# ProPrj_Motorcycle_Controller_2026-08-31.net
KiCad netlist of a schematic drawn in EasyEDA Pro
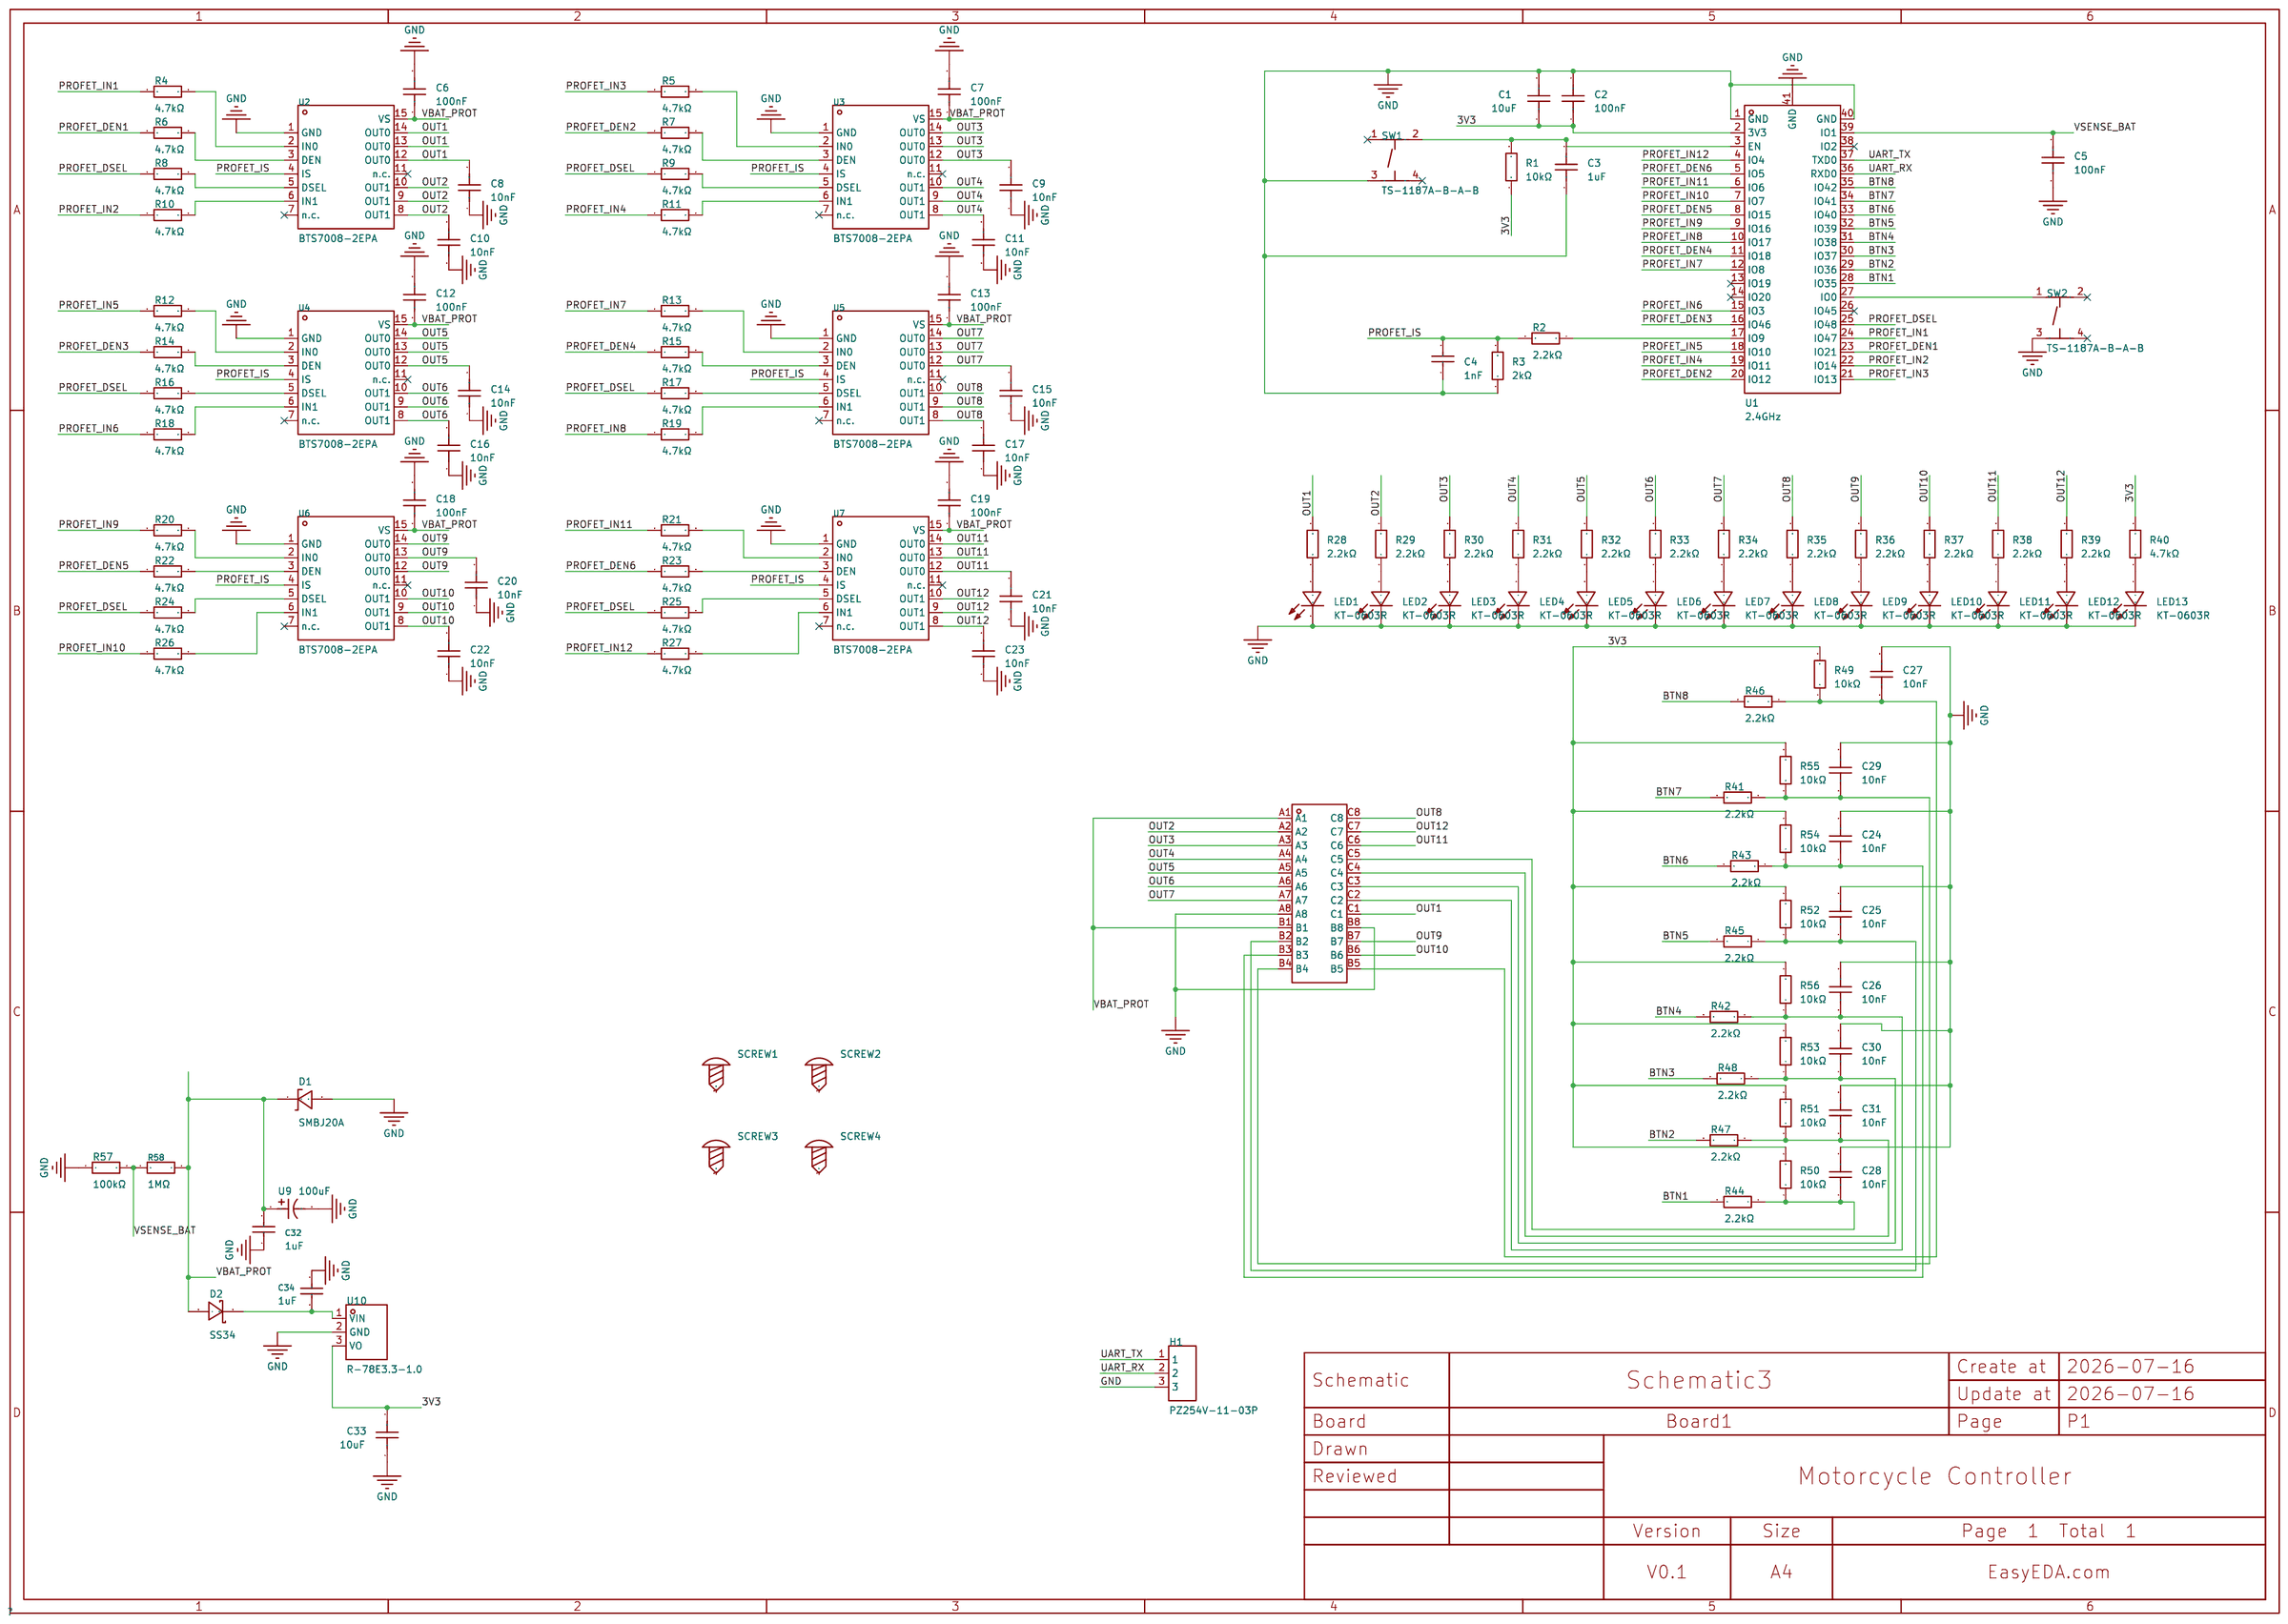
[diagram p0: schematic sheet]

(export (version "E")
  (design (tool "Eeschema 10.0.6"))
  (components
    (comp (ref "C1")
      (value "10uF")
      (footprint "easyedapro:C0603")
      (fields
        (field (name "Manufacturer Part") "CL10A106KP8NNNC")
        (field (name "Manufacturer") "SAMSUNG(三星)")
      )
      (libsource (lib "easyedapro") (part "CL10A106KP8NNNC"))
    )
    (comp (ref "C2")
      (value "100nF")
      (footprint "easyedapro:C0402")
      (fields
        (field (name "Manufacturer Part") "CL05B104KO5NNNC")
        (field (name "Manufacturer") "SAMSUNG(三星)")
      )
      (libsource (lib "easyedapro") (part "CL05B104KO5NNNC"))
    )
    (comp (ref "C3")
      (value "1uF")
      (footprint "easyedapro:C0402")
      (fields
        (field (name "Manufacturer Part") "CL05A105KA5NQNC")
        (field (name "Manufacturer") "SAMSUNG(三星)")
      )
      (libsource (lib "easyedapro") (part "CL05A105KA5NQNC"))
    )
    (comp (ref "C4")
      (value "1nF")
      (footprint "easyedapro:C0402")
      (fields (field (name "Manufacturer Part") "0402B102K500NT") (field (name "Manufacturer") "FH(风华)"))
      (libsource (lib "easyedapro") (part "0402B102K500NT"))
    )
    (comp (ref "C5")
      (value "100nF")
      (footprint "easyedapro:C0402")
      (fields
        (field (name "Manufacturer Part") "CL05B104KO5NNNC")
        (field (name "Manufacturer") "SAMSUNG(三星)")
      )
      (libsource (lib "easyedapro") (part "CL05B104KO5NNNC"))
    )
    (comp (ref "C6")
      (value "100nF")
      (footprint "easyedapro:C0603")
      (fields
        (field (name "Manufacturer Part") "CC0603KRX7R9BB104")
        (field (name "Manufacturer") "YAGEO(国巨)")
      )
      (libsource (lib "easyedapro") (part "CC0603KRX7R9BB104"))
    )
    (comp (ref "C7")
      (value "100nF")
      (footprint "easyedapro:C0603")
      (fields
        (field (name "Manufacturer Part") "CC0603KRX7R9BB104")
        (field (name "Manufacturer") "YAGEO(国巨)")
      )
      (libsource (lib "easyedapro") (part "CC0603KRX7R9BB104"))
    )
    (comp (ref "C8")
      (value "10nF")
      (footprint "easyedapro:C0603")
      (fields (field (name "Manufacturer Part") "0603B103K500NT") (field (name "Manufacturer") "FH(风华)"))
      (libsource (lib "easyedapro") (part "0603B103K500NT"))
    )
    (comp (ref "C9")
      (value "10nF")
      (footprint "easyedapro:C0603")
      (fields (field (name "Manufacturer Part") "0603B103K500NT") (field (name "Manufacturer") "FH(风华)"))
      (libsource (lib "easyedapro") (part "0603B103K500NT"))
    )
    (comp (ref "C10")
      (value "10nF")
      (footprint "easyedapro:C0603")
      (fields (field (name "Manufacturer Part") "0603B103K500NT") (field (name "Manufacturer") "FH(风华)"))
      (libsource (lib "easyedapro") (part "0603B103K500NT"))
    )
    (comp (ref "C11")
      (value "10nF")
      (footprint "easyedapro:C0603")
      (fields (field (name "Manufacturer Part") "0603B103K500NT") (field (name "Manufacturer") "FH(风华)"))
      (libsource (lib "easyedapro") (part "0603B103K500NT"))
    )
    (comp (ref "C12")
      (value "100nF")
      (footprint "easyedapro:C0603")
      (fields
        (field (name "Manufacturer Part") "CC0603KRX7R9BB104")
        (field (name "Manufacturer") "YAGEO(国巨)")
      )
      (libsource (lib "easyedapro") (part "CC0603KRX7R9BB104"))
    )
    (comp (ref "C13")
      (value "100nF")
      (footprint "easyedapro:C0603")
      (fields
        (field (name "Manufacturer Part") "CC0603KRX7R9BB104")
        (field (name "Manufacturer") "YAGEO(国巨)")
      )
      (libsource (lib "easyedapro") (part "CC0603KRX7R9BB104"))
    )
    (comp (ref "C14")
      (value "10nF")
      (footprint "easyedapro:C0603")
      (fields (field (name "Manufacturer Part") "0603B103K500NT") (field (name "Manufacturer") "FH(风华)"))
      (libsource (lib "easyedapro") (part "0603B103K500NT"))
    )
    (comp (ref "C15")
      (value "10nF")
      (footprint "easyedapro:C0603")
      (fields (field (name "Manufacturer Part") "0603B103K500NT") (field (name "Manufacturer") "FH(风华)"))
      (libsource (lib "easyedapro") (part "0603B103K500NT"))
    )
    (comp (ref "C16")
      (value "10nF")
      (footprint "easyedapro:C0603")
      (fields (field (name "Manufacturer Part") "0603B103K500NT") (field (name "Manufacturer") "FH(风华)"))
      (libsource (lib "easyedapro") (part "0603B103K500NT"))
    )
    (comp (ref "C17")
      (value "10nF")
      (footprint "easyedapro:C0603")
      (fields (field (name "Manufacturer Part") "0603B103K500NT") (field (name "Manufacturer") "FH(风华)"))
      (libsource (lib "easyedapro") (part "0603B103K500NT"))
    )
    (comp (ref "C18")
      (value "100nF")
      (footprint "easyedapro:C0603")
      (fields
        (field (name "Manufacturer Part") "CC0603KRX7R9BB104")
        (field (name "Manufacturer") "YAGEO(国巨)")
      )
      (libsource (lib "easyedapro") (part "CC0603KRX7R9BB104"))
    )
    (comp (ref "C19")
      (value "100nF")
      (footprint "easyedapro:C0603")
      (fields
        (field (name "Manufacturer Part") "CC0603KRX7R9BB104")
        (field (name "Manufacturer") "YAGEO(国巨)")
      )
      (libsource (lib "easyedapro") (part "CC0603KRX7R9BB104"))
    )
    (comp (ref "C20")
      (value "10nF")
      (footprint "easyedapro:C0603")
      (fields (field (name "Manufacturer Part") "0603B103K500NT") (field (name "Manufacturer") "FH(风华)"))
      (libsource (lib "easyedapro") (part "0603B103K500NT"))
    )
    (comp (ref "C21")
      (value "10nF")
      (footprint "easyedapro:C0603")
      (fields (field (name "Manufacturer Part") "0603B103K500NT") (field (name "Manufacturer") "FH(风华)"))
      (libsource (lib "easyedapro") (part "0603B103K500NT"))
    )
    (comp (ref "C22")
      (value "10nF")
      (footprint "easyedapro:C0603")
      (fields (field (name "Manufacturer Part") "0603B103K500NT") (field (name "Manufacturer") "FH(风华)"))
      (libsource (lib "easyedapro") (part "0603B103K500NT"))
    )
    (comp (ref "C23")
      (value "10nF")
      (footprint "easyedapro:C0603")
      (fields (field (name "Manufacturer Part") "0603B103K500NT") (field (name "Manufacturer") "FH(风华)"))
      (libsource (lib "easyedapro") (part "0603B103K500NT"))
    )
    (comp (ref "C24")
      (value "10nF")
      (footprint "easyedapro:C0603")
      (fields (field (name "Manufacturer Part") "0603B103K500NT") (field (name "Manufacturer") "FH(风华)"))
      (libsource (lib "easyedapro") (part "0603B103K500NT"))
    )
    (comp (ref "C25")
      (value "10nF")
      (footprint "easyedapro:C0603")
      (fields (field (name "Manufacturer Part") "0603B103K500NT") (field (name "Manufacturer") "FH(风华)"))
      (libsource (lib "easyedapro") (part "0603B103K500NT"))
    )
    (comp (ref "C26")
      (value "10nF")
      (footprint "easyedapro:C0603")
      (fields (field (name "Manufacturer Part") "0603B103K500NT") (field (name "Manufacturer") "FH(风华)"))
      (libsource (lib "easyedapro") (part "0603B103K500NT"))
    )
    (comp (ref "C27")
      (value "10nF")
      (footprint "easyedapro:C0603")
      (fields (field (name "Manufacturer Part") "0603B103K500NT") (field (name "Manufacturer") "FH(风华)"))
      (libsource (lib "easyedapro") (part "0603B103K500NT"))
    )
    (comp (ref "C28")
      (value "10nF")
      (footprint "easyedapro:C0603")
      (fields (field (name "Manufacturer Part") "0603B103K500NT") (field (name "Manufacturer") "FH(风华)"))
      (libsource (lib "easyedapro") (part "0603B103K500NT"))
    )
    (comp (ref "C29")
      (value "10nF")
      (footprint "easyedapro:C0603")
      (fields (field (name "Manufacturer Part") "0603B103K500NT") (field (name "Manufacturer") "FH(风华)"))
      (libsource (lib "easyedapro") (part "0603B103K500NT"))
    )
    (comp (ref "C30")
      (value "10nF")
      (footprint "easyedapro:C0603")
      (fields (field (name "Manufacturer Part") "0603B103K500NT") (field (name "Manufacturer") "FH(风华)"))
      (libsource (lib "easyedapro") (part "0603B103K500NT"))
    )
    (comp (ref "C31")
      (value "10nF")
      (footprint "easyedapro:C0603")
      (fields (field (name "Manufacturer Part") "0603B103K500NT") (field (name "Manufacturer") "FH(风华)"))
      (libsource (lib "easyedapro") (part "0603B103K500NT"))
    )
    (comp (ref "C32")
      (value "1uF")
      (footprint "easyedapro:C0805")
      (fields
        (field (name "Manufacturer Part") "CL21B105KBFNNNE")
        (field (name "Manufacturer") "SAMSUNG(三星)")
      )
      (libsource (lib "easyedapro") (part "CL21B105KBFNNNE"))
    )
    (comp (ref "C33")
      (value "10uF")
      (footprint "easyedapro:C0603")
      (fields
        (field (name "Manufacturer Part") "CL10A106KP8NNNC")
        (field (name "Manufacturer") "SAMSUNG(三星)")
      )
      (libsource (lib "easyedapro") (part "CL10A106KP8NNNC"))
    )
    (comp (ref "C34")
      (value "1uF")
      (footprint "easyedapro:C0805")
      (fields
        (field (name "Manufacturer Part") "CL21B105KBFNNNE")
        (field (name "Manufacturer") "SAMSUNG(三星)")
      )
      (libsource (lib "easyedapro") (part "CL21B105KBFNNNE"))
    )
    (comp (ref "CN3")
      (value "HCCPHPE24BKA90F")
      (footprint "easyedapro:CONN-TH_HCCPHPE24BKA90F")
      (fields (field (name "Manufacturer") "Aptiv(Delphi)"))
      (libsource (lib "easyedapro") (part "HCCPHPE24BKA90F_C5349068"))
    )
    (comp (ref "D1")
      (value "SMBJ20A")
      (footprint "easyedapro:SMB_L4.6-W3.6-LS5.3-RD")
      (fields (field (name "Manufacturer") "MDD(辰达半导体)"))
      (libsource (lib "easyedapro") (part "SMBJ20A_C364296"))
    )
    (comp (ref "D2")
      (value "SS34")
      (footprint "easyedapro:SMA_L4.3-W2.6-LS5.2-RD")
      (fields (field (name "Manufacturer") "MDD(辰达半导体)"))
      (libsource (lib "easyedapro") (part "SS34_C8678"))
    )
    (comp (ref "H1")
      (value "PZ254V-11-03P")
      (footprint "easyedapro:HDR-TH_3P-P2.54-V-M_PZ254V-11-03P")
      (fields (field (name "Manufacturer") "XFCN(兴飞)"))
      (libsource (lib "easyedapro") (part "PZ254V-11-03P_C2937625"))
    )
    (comp (ref "LED1")
      (value "KT-0603R")
      (footprint "easyedapro:LED-SMD_L1.6-W0.8-R-RD")
      (fields (field (name "Manufacturer") "KENTO"))
      (libsource (lib "easyedapro") (part "KT-0603R"))
    )
    (comp (ref "LED2")
      (value "KT-0603R")
      (footprint "easyedapro:LED-SMD_L1.6-W0.8-R-RD")
      (fields (field (name "Manufacturer") "KENTO"))
      (libsource (lib "easyedapro") (part "KT-0603R"))
    )
    (comp (ref "LED3")
      (value "KT-0603R")
      (footprint "easyedapro:LED-SMD_L1.6-W0.8-R-RD")
      (fields (field (name "Manufacturer") "KENTO"))
      (libsource (lib "easyedapro") (part "KT-0603R"))
    )
    (comp (ref "LED4")
      (value "KT-0603R")
      (footprint "easyedapro:LED-SMD_L1.6-W0.8-R-RD")
      (fields (field (name "Manufacturer") "KENTO"))
      (libsource (lib "easyedapro") (part "KT-0603R"))
    )
    (comp (ref "LED5")
      (value "KT-0603R")
      (footprint "easyedapro:LED-SMD_L1.6-W0.8-R-RD")
      (fields (field (name "Manufacturer") "KENTO"))
      (libsource (lib "easyedapro") (part "KT-0603R"))
    )
    (comp (ref "LED6")
      (value "KT-0603R")
      (footprint "easyedapro:LED-SMD_L1.6-W0.8-R-RD")
      (fields (field (name "Manufacturer") "KENTO"))
      (libsource (lib "easyedapro") (part "KT-0603R"))
    )
    (comp (ref "LED7")
      (value "KT-0603R")
      (footprint "easyedapro:LED-SMD_L1.6-W0.8-R-RD")
      (fields (field (name "Manufacturer") "KENTO"))
      (libsource (lib "easyedapro") (part "KT-0603R"))
    )
    (comp (ref "LED8")
      (value "KT-0603R")
      (footprint "easyedapro:LED-SMD_L1.6-W0.8-R-RD")
      (fields (field (name "Manufacturer") "KENTO"))
      (libsource (lib "easyedapro") (part "KT-0603R"))
    )
    (comp (ref "LED9")
      (value "KT-0603R")
      (footprint "easyedapro:LED-SMD_L1.6-W0.8-R-RD")
      (fields (field (name "Manufacturer") "KENTO"))
      (libsource (lib "easyedapro") (part "KT-0603R"))
    )
    (comp (ref "LED10")
      (value "KT-0603R")
      (footprint "easyedapro:LED-SMD_L1.6-W0.8-R-RD")
      (fields (field (name "Manufacturer") "KENTO"))
      (libsource (lib "easyedapro") (part "KT-0603R"))
    )
    (comp (ref "LED11")
      (value "KT-0603R")
      (footprint "easyedapro:LED-SMD_L1.6-W0.8-R-RD")
      (fields (field (name "Manufacturer") "KENTO"))
      (libsource (lib "easyedapro") (part "KT-0603R"))
    )
    (comp (ref "LED12")
      (value "KT-0603R")
      (footprint "easyedapro:LED-SMD_L1.6-W0.8-R-RD")
      (fields (field (name "Manufacturer") "KENTO"))
      (libsource (lib "easyedapro") (part "KT-0603R"))
    )
    (comp (ref "LED13")
      (value "KT-0603R")
      (footprint "easyedapro:LED-SMD_L1.6-W0.8-R-RD")
      (fields (field (name "Manufacturer") "KENTO"))
      (libsource (lib "easyedapro") (part "KT-0603R"))
    )
    (comp (ref "R1")
      (value "10kΩ")
      (footprint "easyedapro:R0402")
      (fields (field (name "Manufacturer Part") "RC0402FR-0710KL") (field (name "Manufacturer") "YAGEO(国巨)"))
      (libsource (lib "easyedapro") (part "RC0402FR-0710KL"))
    )
    (comp (ref "R2")
      (value "2.2kΩ")
      (footprint "easyedapro:R0603")
      (fields
        (field (name "Manufacturer Part") "0603WAF2201T5E")
        (field (name "Manufacturer") "UNI-ROYAL(厚声)")
      )
      (libsource (lib "easyedapro") (part "0603WAF2201T5E"))
    )
    (comp (ref "R3")
      (value "2kΩ")
      (footprint "easyedapro:R0603")
      (fields
        (field (name "Manufacturer Part") "0603WAF2001T5E")
        (field (name "Manufacturer") "UNI-ROYAL(厚声)")
      )
      (libsource (lib "easyedapro") (part "0603WAF2001T5E"))
    )
    (comp (ref "R4")
      (value "4.7kΩ")
      (footprint "easyedapro:R0603")
      (fields
        (field (name "Manufacturer Part") "0603WAF4701T5E")
        (field (name "Manufacturer") "UNI-ROYAL(厚声)")
      )
      (libsource (lib "easyedapro") (part "0603WAF4701T5E"))
    )
    (comp (ref "R5")
      (value "4.7kΩ")
      (footprint "easyedapro:R0603")
      (fields
        (field (name "Manufacturer Part") "0603WAF4701T5E")
        (field (name "Manufacturer") "UNI-ROYAL(厚声)")
      )
      (libsource (lib "easyedapro") (part "0603WAF4701T5E"))
    )
    (comp (ref "R6")
      (value "4.7kΩ")
      (footprint "easyedapro:R0603")
      (fields
        (field (name "Manufacturer Part") "0603WAF4701T5E")
        (field (name "Manufacturer") "UNI-ROYAL(厚声)")
      )
      (libsource (lib "easyedapro") (part "0603WAF4701T5E"))
    )
    (comp (ref "R7")
      (value "4.7kΩ")
      (footprint "easyedapro:R0603")
      (fields
        (field (name "Manufacturer Part") "0603WAF4701T5E")
        (field (name "Manufacturer") "UNI-ROYAL(厚声)")
      )
      (libsource (lib "easyedapro") (part "0603WAF4701T5E"))
    )
    (comp (ref "R8")
      (value "4.7kΩ")
      (footprint "easyedapro:R0603")
      (fields
        (field (name "Manufacturer Part") "0603WAF4701T5E")
        (field (name "Manufacturer") "UNI-ROYAL(厚声)")
      )
      (libsource (lib "easyedapro") (part "0603WAF4701T5E"))
    )
    (comp (ref "R9")
      (value "4.7kΩ")
      (footprint "easyedapro:R0603")
      (fields
        (field (name "Manufacturer Part") "0603WAF4701T5E")
        (field (name "Manufacturer") "UNI-ROYAL(厚声)")
      )
      (libsource (lib "easyedapro") (part "0603WAF4701T5E"))
    )
    (comp (ref "R10")
      (value "4.7kΩ")
      (footprint "easyedapro:R0603")
      (fields
        (field (name "Manufacturer Part") "0603WAF4701T5E")
        (field (name "Manufacturer") "UNI-ROYAL(厚声)")
      )
      (libsource (lib "easyedapro") (part "0603WAF4701T5E"))
    )
    (comp (ref "R11")
      (value "4.7kΩ")
      (footprint "easyedapro:R0603")
      (fields
        (field (name "Manufacturer Part") "0603WAF4701T5E")
        (field (name "Manufacturer") "UNI-ROYAL(厚声)")
      )
      (libsource (lib "easyedapro") (part "0603WAF4701T5E"))
    )
    (comp (ref "R12")
      (value "4.7kΩ")
      (footprint "easyedapro:R0603")
      (fields
        (field (name "Manufacturer Part") "0603WAF4701T5E")
        (field (name "Manufacturer") "UNI-ROYAL(厚声)")
      )
      (libsource (lib "easyedapro") (part "0603WAF4701T5E"))
    )
    (comp (ref "R13")
      (value "4.7kΩ")
      (footprint "easyedapro:R0603")
      (fields
        (field (name "Manufacturer Part") "0603WAF4701T5E")
        (field (name "Manufacturer") "UNI-ROYAL(厚声)")
      )
      (libsource (lib "easyedapro") (part "0603WAF4701T5E"))
    )
    (comp (ref "R14")
      (value "4.7kΩ")
      (footprint "easyedapro:R0603")
      (fields
        (field (name "Manufacturer Part") "0603WAF4701T5E")
        (field (name "Manufacturer") "UNI-ROYAL(厚声)")
      )
      (libsource (lib "easyedapro") (part "0603WAF4701T5E"))
    )
    (comp (ref "R15")
      (value "4.7kΩ")
      (footprint "easyedapro:R0603")
      (fields
        (field (name "Manufacturer Part") "0603WAF4701T5E")
        (field (name "Manufacturer") "UNI-ROYAL(厚声)")
      )
      (libsource (lib "easyedapro") (part "0603WAF4701T5E"))
    )
    (comp (ref "R16")
      (value "4.7kΩ")
      (footprint "easyedapro:R0603")
      (fields
        (field (name "Manufacturer Part") "0603WAF4701T5E")
        (field (name "Manufacturer") "UNI-ROYAL(厚声)")
      )
      (libsource (lib "easyedapro") (part "0603WAF4701T5E"))
    )
    (comp (ref "R17")
      (value "4.7kΩ")
      (footprint "easyedapro:R0603")
      (fields
        (field (name "Manufacturer Part") "0603WAF4701T5E")
        (field (name "Manufacturer") "UNI-ROYAL(厚声)")
      )
      (libsource (lib "easyedapro") (part "0603WAF4701T5E"))
    )
    (comp (ref "R18")
      (value "4.7kΩ")
      (footprint "easyedapro:R0603")
      (fields
        (field (name "Manufacturer Part") "0603WAF4701T5E")
        (field (name "Manufacturer") "UNI-ROYAL(厚声)")
      )
      (libsource (lib "easyedapro") (part "0603WAF4701T5E"))
    )
    (comp (ref "R19")
      (value "4.7kΩ")
      (footprint "easyedapro:R0603")
      (fields
        (field (name "Manufacturer Part") "0603WAF4701T5E")
        (field (name "Manufacturer") "UNI-ROYAL(厚声)")
      )
      (libsource (lib "easyedapro") (part "0603WAF4701T5E"))
    )
    (comp (ref "R20")
      (value "4.7kΩ")
      (footprint "easyedapro:R0603")
      (fields
        (field (name "Manufacturer Part") "0603WAF4701T5E")
        (field (name "Manufacturer") "UNI-ROYAL(厚声)")
      )
      (libsource (lib "easyedapro") (part "0603WAF4701T5E"))
    )
    (comp (ref "R21")
      (value "4.7kΩ")
      (footprint "easyedapro:R0603")
      (fields
        (field (name "Manufacturer Part") "0603WAF4701T5E")
        (field (name "Manufacturer") "UNI-ROYAL(厚声)")
      )
      (libsource (lib "easyedapro") (part "0603WAF4701T5E"))
    )
    (comp (ref "R22")
      (value "4.7kΩ")
      (footprint "easyedapro:R0603")
      (fields
        (field (name "Manufacturer Part") "0603WAF4701T5E")
        (field (name "Manufacturer") "UNI-ROYAL(厚声)")
      )
      (libsource (lib "easyedapro") (part "0603WAF4701T5E"))
    )
    (comp (ref "R23")
      (value "4.7kΩ")
      (footprint "easyedapro:R0603")
      (fields
        (field (name "Manufacturer Part") "0603WAF4701T5E")
        (field (name "Manufacturer") "UNI-ROYAL(厚声)")
      )
      (libsource (lib "easyedapro") (part "0603WAF4701T5E"))
    )
    (comp (ref "R24")
      (value "4.7kΩ")
      (footprint "easyedapro:R0603")
      (fields
        (field (name "Manufacturer Part") "0603WAF4701T5E")
        (field (name "Manufacturer") "UNI-ROYAL(厚声)")
      )
      (libsource (lib "easyedapro") (part "0603WAF4701T5E"))
    )
    (comp (ref "R25")
      (value "4.7kΩ")
      (footprint "easyedapro:R0603")
      (fields
        (field (name "Manufacturer Part") "0603WAF4701T5E")
        (field (name "Manufacturer") "UNI-ROYAL(厚声)")
      )
      (libsource (lib "easyedapro") (part "0603WAF4701T5E"))
    )
    (comp (ref "R26")
      (value "4.7kΩ")
      (footprint "easyedapro:R0603")
      (fields
        (field (name "Manufacturer Part") "0603WAF4701T5E")
        (field (name "Manufacturer") "UNI-ROYAL(厚声)")
      )
      (libsource (lib "easyedapro") (part "0603WAF4701T5E"))
    )
    (comp (ref "R27")
      (value "4.7kΩ")
      (footprint "easyedapro:R0603")
      (fields
        (field (name "Manufacturer Part") "0603WAF4701T5E")
        (field (name "Manufacturer") "UNI-ROYAL(厚声)")
      )
      (libsource (lib "easyedapro") (part "0603WAF4701T5E"))
    )
    (comp (ref "R28")
      (value "2.2kΩ")
      (footprint "easyedapro:R0603")
      (fields
        (field (name "Manufacturer Part") "0603WAF2201T5E")
        (field (name "Manufacturer") "UNI-ROYAL(厚声)")
      )
      (libsource (lib "easyedapro") (part "0603WAF2201T5E"))
    )
    (comp (ref "R29")
      (value "2.2kΩ")
      (footprint "easyedapro:R0603")
      (fields
        (field (name "Manufacturer Part") "0603WAF2201T5E")
        (field (name "Manufacturer") "UNI-ROYAL(厚声)")
      )
      (libsource (lib "easyedapro") (part "0603WAF2201T5E"))
    )
    (comp (ref "R30")
      (value "2.2kΩ")
      (footprint "easyedapro:R0603")
      (fields
        (field (name "Manufacturer Part") "0603WAF2201T5E")
        (field (name "Manufacturer") "UNI-ROYAL(厚声)")
      )
      (libsource (lib "easyedapro") (part "0603WAF2201T5E"))
    )
    (comp (ref "R31")
      (value "2.2kΩ")
      (footprint "easyedapro:R0603")
      (fields
        (field (name "Manufacturer Part") "0603WAF2201T5E")
        (field (name "Manufacturer") "UNI-ROYAL(厚声)")
      )
      (libsource (lib "easyedapro") (part "0603WAF2201T5E"))
    )
    (comp (ref "R32")
      (value "2.2kΩ")
      (footprint "easyedapro:R0603")
      (fields
        (field (name "Manufacturer Part") "0603WAF2201T5E")
        (field (name "Manufacturer") "UNI-ROYAL(厚声)")
      )
      (libsource (lib "easyedapro") (part "0603WAF2201T5E"))
    )
    (comp (ref "R33")
      (value "2.2kΩ")
      (footprint "easyedapro:R0603")
      (fields
        (field (name "Manufacturer Part") "0603WAF2201T5E")
        (field (name "Manufacturer") "UNI-ROYAL(厚声)")
      )
      (libsource (lib "easyedapro") (part "0603WAF2201T5E"))
    )
    (comp (ref "R34")
      (value "2.2kΩ")
      (footprint "easyedapro:R0603")
      (fields
        (field (name "Manufacturer Part") "0603WAF2201T5E")
        (field (name "Manufacturer") "UNI-ROYAL(厚声)")
      )
      (libsource (lib "easyedapro") (part "0603WAF2201T5E"))
    )
    (comp (ref "R35")
      (value "2.2kΩ")
      (footprint "easyedapro:R0603")
      (fields
        (field (name "Manufacturer Part") "0603WAF2201T5E")
        (field (name "Manufacturer") "UNI-ROYAL(厚声)")
      )
      (libsource (lib "easyedapro") (part "0603WAF2201T5E"))
    )
    (comp (ref "R36")
      (value "2.2kΩ")
      (footprint "easyedapro:R0603")
      (fields
        (field (name "Manufacturer Part") "0603WAF2201T5E")
        (field (name "Manufacturer") "UNI-ROYAL(厚声)")
      )
      (libsource (lib "easyedapro") (part "0603WAF2201T5E"))
    )
    (comp (ref "R37")
      (value "2.2kΩ")
      (footprint "easyedapro:R0603")
      (fields
        (field (name "Manufacturer Part") "0603WAF2201T5E")
        (field (name "Manufacturer") "UNI-ROYAL(厚声)")
      )
      (libsource (lib "easyedapro") (part "0603WAF2201T5E"))
    )
    (comp (ref "R38")
      (value "2.2kΩ")
      (footprint "easyedapro:R0603")
      (fields
        (field (name "Manufacturer Part") "0603WAF2201T5E")
        (field (name "Manufacturer") "UNI-ROYAL(厚声)")
      )
      (libsource (lib "easyedapro") (part "0603WAF2201T5E"))
    )
    (comp (ref "R39")
      (value "2.2kΩ")
      (footprint "easyedapro:R0603")
      (fields
        (field (name "Manufacturer Part") "0603WAF2201T5E")
        (field (name "Manufacturer") "UNI-ROYAL(厚声)")
      )
      (libsource (lib "easyedapro") (part "0603WAF2201T5E"))
    )
    (comp (ref "R40")
      (value "4.7kΩ")
      (footprint "easyedapro:R0603")
      (fields
        (field (name "Manufacturer Part") "0603WAF4701T5E")
        (field (name "Manufacturer") "UNI-ROYAL(厚声)")
      )
      (libsource (lib "easyedapro") (part "0603WAF4701T5E"))
    )
    (comp (ref "R41")
      (value "2.2kΩ")
      (footprint "easyedapro:R0603")
      (fields
        (field (name "Manufacturer Part") "0603WAF2201T5E")
        (field (name "Manufacturer") "UNI-ROYAL(厚声)")
      )
      (libsource (lib "easyedapro") (part "0603WAF2201T5E"))
    )
    (comp (ref "R42")
      (value "2.2kΩ")
      (footprint "easyedapro:R0603")
      (fields
        (field (name "Manufacturer Part") "0603WAF2201T5E")
        (field (name "Manufacturer") "UNI-ROYAL(厚声)")
      )
      (libsource (lib "easyedapro") (part "0603WAF2201T5E"))
    )
    (comp (ref "R43")
      (value "2.2kΩ")
      (footprint "easyedapro:R0603")
      (fields
        (field (name "Manufacturer Part") "0603WAF2201T5E")
        (field (name "Manufacturer") "UNI-ROYAL(厚声)")
      )
      (libsource (lib "easyedapro") (part "0603WAF2201T5E"))
    )
    (comp (ref "R44")
      (value "2.2kΩ")
      (footprint "easyedapro:R0603")
      (fields
        (field (name "Manufacturer Part") "0603WAF2201T5E")
        (field (name "Manufacturer") "UNI-ROYAL(厚声)")
      )
      (libsource (lib "easyedapro") (part "0603WAF2201T5E"))
    )
    (comp (ref "R45")
      (value "2.2kΩ")
      (footprint "easyedapro:R0603")
      (fields
        (field (name "Manufacturer Part") "0603WAF2201T5E")
        (field (name "Manufacturer") "UNI-ROYAL(厚声)")
      )
      (libsource (lib "easyedapro") (part "0603WAF2201T5E"))
    )
    (comp (ref "R46")
      (value "2.2kΩ")
      (footprint "easyedapro:R0603")
      (fields
        (field (name "Manufacturer Part") "0603WAF2201T5E")
        (field (name "Manufacturer") "UNI-ROYAL(厚声)")
      )
      (libsource (lib "easyedapro") (part "0603WAF2201T5E"))
    )
    (comp (ref "R47")
      (value "2.2kΩ")
      (footprint "easyedapro:R0603")
      (fields
        (field (name "Manufacturer Part") "0603WAF2201T5E")
        (field (name "Manufacturer") "UNI-ROYAL(厚声)")
      )
      (libsource (lib "easyedapro") (part "0603WAF2201T5E"))
    )
    (comp (ref "R48")
      (value "2.2kΩ")
      (footprint "easyedapro:R0603")
      (fields
        (field (name "Manufacturer Part") "0603WAF2201T5E")
        (field (name "Manufacturer") "UNI-ROYAL(厚声)")
      )
      (libsource (lib "easyedapro") (part "0603WAF2201T5E"))
    )
    (comp (ref "R49")
      (value "10kΩ")
      (footprint "easyedapro:R0402")
      (fields (field (name "Manufacturer Part") "RC0402FR-0710KL") (field (name "Manufacturer") "YAGEO(国巨)"))
      (libsource (lib "easyedapro") (part "RC0402FR-0710KL"))
    )
    (comp (ref "R50")
      (value "10kΩ")
      (footprint "easyedapro:R0402")
      (fields (field (name "Manufacturer Part") "RC0402FR-0710KL") (field (name "Manufacturer") "YAGEO(国巨)"))
      (libsource (lib "easyedapro") (part "RC0402FR-0710KL"))
    )
    (comp (ref "R51")
      (value "10kΩ")
      (footprint "easyedapro:R0402")
      (fields (field (name "Manufacturer Part") "RC0402FR-0710KL") (field (name "Manufacturer") "YAGEO(国巨)"))
      (libsource (lib "easyedapro") (part "RC0402FR-0710KL"))
    )
    (comp (ref "R52")
      (value "10kΩ")
      (footprint "easyedapro:R0402")
      (fields (field (name "Manufacturer Part") "RC0402FR-0710KL") (field (name "Manufacturer") "YAGEO(国巨)"))
      (libsource (lib "easyedapro") (part "RC0402FR-0710KL"))
    )
    (comp (ref "R53")
      (value "10kΩ")
      (footprint "easyedapro:R0402")
      (fields (field (name "Manufacturer Part") "RC0402FR-0710KL") (field (name "Manufacturer") "YAGEO(国巨)"))
      (libsource (lib "easyedapro") (part "RC0402FR-0710KL"))
    )
    (comp (ref "R54")
      (value "10kΩ")
      (footprint "easyedapro:R0402")
      (fields (field (name "Manufacturer Part") "RC0402FR-0710KL") (field (name "Manufacturer") "YAGEO(国巨)"))
      (libsource (lib "easyedapro") (part "RC0402FR-0710KL"))
    )
    (comp (ref "R55")
      (value "10kΩ")
      (footprint "easyedapro:R0402")
      (fields (field (name "Manufacturer Part") "RC0402FR-0710KL") (field (name "Manufacturer") "YAGEO(国巨)"))
      (libsource (lib "easyedapro") (part "RC0402FR-0710KL"))
    )
    (comp (ref "R56")
      (value "10kΩ")
      (footprint "easyedapro:R0402")
      (fields (field (name "Manufacturer Part") "RC0402FR-0710KL") (field (name "Manufacturer") "YAGEO(国巨)"))
      (libsource (lib "easyedapro") (part "RC0402FR-0710KL"))
    )
    (comp (ref "R57")
      (value "100kΩ")
      (footprint "easyedapro:R0603")
      (fields
        (field (name "Manufacturer Part") "0603WAF1003T5E")
        (field (name "Manufacturer") "UNI-ROYAL(厚声)")
      )
      (libsource (lib "easyedapro") (part "0603WAF1003T5E"))
    )
    (comp (ref "R58")
      (value "1MΩ")
      (footprint "easyedapro:R0603")
      (fields
        (field (name "Manufacturer Part") "0603WAF1004T5E")
        (field (name "Manufacturer") "UNI-ROYAL(厚声)")
      )
      (libsource (lib "easyedapro") (part "0603WAF1004T5E"))
    )
    (comp (ref "SCREW1")
      (value "~")
      (footprint "easyedapro:Screw-Hole-M3")
      (libsource (lib "easyedapro") (part "Screw-Hole"))
    )
    (comp (ref "SCREW2")
      (value "~")
      (footprint "easyedapro:Screw-Hole-M3")
      (libsource (lib "easyedapro") (part "Screw-Hole"))
    )
    (comp (ref "SCREW3")
      (value "~")
      (footprint "easyedapro:Screw-Hole-M3")
      (libsource (lib "easyedapro") (part "Screw-Hole"))
    )
    (comp (ref "SCREW4")
      (value "~")
      (footprint "easyedapro:Screw-Hole-M3")
      (libsource (lib "easyedapro") (part "Screw-Hole"))
    )
    (comp (ref "SW1")
      (value "TS-1187A-B-A-B")
      (footprint "easyedapro:SW-SMD_4P-L5.1-W5.1-P3.70-LS6.5-TL_H1.5")
      (fields (field (name "Manufacturer") "XKB Connection(中国星坤)"))
      (libsource (lib "easyedapro") (part "TS-1187A-B-A-B"))
    )
    (comp (ref "SW2")
      (value "TS-1187A-B-A-B")
      (footprint "easyedapro:SW-SMD_4P-L5.1-W5.1-P3.70-LS6.5-TL_H1.5")
      (fields (field (name "Manufacturer") "XKB Connection(中国星坤)"))
      (libsource (lib "easyedapro") (part "TS-1187A-B-A-B"))
    )
    (comp (ref "U1")
      (value "2.4GHz")
      (footprint "easyedapro:WIFIM-SMD_ESP32-S3-WROOM-1-N8")
      (fields
        (field (name "Manufacturer Part") "ESP32-S3-WROOM-1-N4")
        (field (name "Manufacturer") "ESPRESSIF(乐鑫)")
      )
      (libsource (lib "easyedapro") (part "ESP32-S3-WROOM-1-N4"))
    )
    (comp (ref "U2")
      (value "BTS7008-2EPA")
      (footprint "easyedapro:PG-TSDSO-14_L4.9-W3.9-P0.65-LS6.0-BL-EP")
      (fields (field (name "Manufacturer") "Infineon(英飞凌)"))
      (libsource (lib "easyedapro") (part "BTS7008-2EPA"))
    )
    (comp (ref "U3")
      (value "BTS7008-2EPA")
      (footprint "easyedapro:PG-TSDSO-14_L4.9-W3.9-P0.65-LS6.0-BL-EP")
      (fields (field (name "Manufacturer") "Infineon(英飞凌)"))
      (libsource (lib "easyedapro") (part "BTS7008-2EPA"))
    )
    (comp (ref "U4")
      (value "BTS7008-2EPA")
      (footprint "easyedapro:PG-TSDSO-14_L4.9-W3.9-P0.65-LS6.0-BL-EP")
      (fields (field (name "Manufacturer") "Infineon(英飞凌)"))
      (libsource (lib "easyedapro") (part "BTS7008-2EPA"))
    )
    (comp (ref "U5")
      (value "BTS7008-2EPA")
      (footprint "easyedapro:PG-TSDSO-14_L4.9-W3.9-P0.65-LS6.0-BL-EP")
      (fields (field (name "Manufacturer") "Infineon(英飞凌)"))
      (libsource (lib "easyedapro") (part "BTS7008-2EPA"))
    )
    (comp (ref "U6")
      (value "BTS7008-2EPA")
      (footprint "easyedapro:PG-TSDSO-14_L4.9-W3.9-P0.65-LS6.0-BL-EP")
      (fields (field (name "Manufacturer") "Infineon(英飞凌)"))
      (libsource (lib "easyedapro") (part "BTS7008-2EPA"))
    )
    (comp (ref "U7")
      (value "BTS7008-2EPA")
      (footprint "easyedapro:PG-TSDSO-14_L4.9-W3.9-P0.65-LS6.0-BL-EP")
      (fields (field (name "Manufacturer") "Infineon(英飞凌)"))
      (libsource (lib "easyedapro") (part "BTS7008-2EPA"))
    )
    (comp (ref "U9")
      (value "100uF")
      (footprint "easyedapro:CAP-SMD_BD8.0-L8.3-W8.3-LS9.1-FD")
      (fields
        (field (name "Manufacturer Part") "RVT1H101M0810 100UF 50V")
        (field (name "Manufacturer") "DMBJ(振宝佳)")
      )
      (libsource (lib "easyedapro") (part "RVT1H101M0810 100UF 50V"))
    )
    (comp (ref "U10")
      (value "R-78E3.3-1.0")
      (footprint "easyedapro:PWRM-TH_R-78EXX-1.0")
      (fields (field (name "Manufacturer") "YLPTEC(易川)"))
      (libsource (lib "easyedapro") (part "R-78E3.3-1.0"))
    )
  )
  (nets
    (net (code "1") (name "/3V3") (class "Default")
      (node (ref "C1") (pin "1") (pinfunction "1_1") (pintype "unspecified"))
      (node (ref "C2") (pin "1") (pinfunction "1_1") (pintype "unspecified"))
      (node (ref "C33") (pin "2") (pinfunction "2_2") (pintype "unspecified"))
      (node (ref "R1") (pin "1") (pinfunction "1_1") (pintype "input"))
      (node (ref "R40") (pin "2") (pinfunction "2_2") (pintype "input"))
      (node (ref "R49") (pin "2") (pinfunction "2_2") (pintype "input"))
      (node (ref "R50") (pin "2") (pinfunction "2_2") (pintype "input"))
      (node (ref "R51") (pin "2") (pinfunction "2_2") (pintype "input"))
      (node (ref "R52") (pin "2") (pinfunction "2_2") (pintype "input"))
      (node (ref "R53") (pin "2") (pinfunction "2_2") (pintype "input"))
      (node (ref "R54") (pin "2") (pinfunction "2_2") (pintype "input"))
      (node (ref "R55") (pin "2") (pinfunction "2_2") (pintype "input"))
      (node (ref "R56") (pin "2") (pinfunction "2_2") (pintype "input"))
      (node (ref "U1") (pin "2") (pinfunction "3V3_2") (pintype "unspecified"))
      (node (ref "U10") (pin "3") (pinfunction "VO_3") (pintype "unspecified"))
    )
    (net (code "2") (name "/BTN1") (class "Default")
      (node (ref "R44") (pin "2") (pinfunction "2_2") (pintype "input"))
      (node (ref "U1") (pin "28") (pinfunction "IO35_28") (pintype "unspecified"))
    )
    (net (code "3") (name "/BTN2") (class "Default")
      (node (ref "R47") (pin "2") (pinfunction "2_2") (pintype "input"))
      (node (ref "U1") (pin "29") (pinfunction "IO36_29") (pintype "unspecified"))
    )
    (net (code "4") (name "/BTN3") (class "Default")
      (node (ref "R48") (pin "2") (pinfunction "2_2") (pintype "input"))
      (node (ref "U1") (pin "30") (pinfunction "IO37_30") (pintype "unspecified"))
    )
    (net (code "5") (name "/BTN4") (class "Default")
      (node (ref "R42") (pin "2") (pinfunction "2_2") (pintype "input"))
      (node (ref "U1") (pin "31") (pinfunction "IO38_31") (pintype "unspecified"))
    )
    (net (code "6") (name "/BTN5") (class "Default")
      (node (ref "R45") (pin "2") (pinfunction "2_2") (pintype "input"))
      (node (ref "U1") (pin "32") (pinfunction "IO39_32") (pintype "unspecified"))
    )
    (net (code "7") (name "/BTN6") (class "Default")
      (node (ref "R43") (pin "2") (pinfunction "2_2") (pintype "input"))
      (node (ref "U1") (pin "33") (pinfunction "IO40_33") (pintype "unspecified"))
    )
    (net (code "8") (name "/BTN7") (class "Default")
      (node (ref "R41") (pin "2") (pinfunction "2_2") (pintype "input"))
      (node (ref "U1") (pin "34") (pinfunction "IO41_34") (pintype "unspecified"))
    )
    (net (code "9") (name "/BTN8") (class "Default")
      (node (ref "R46") (pin "2") (pinfunction "2_2") (pintype "input"))
      (node (ref "U1") (pin "35") (pinfunction "IO42_35") (pintype "unspecified"))
    )
    (net (code "10") (name "/OUT1") (class "Default")
      (node (ref "C8") (pin "2") (pinfunction "2_2") (pintype "unspecified"))
      (node (ref "CN3") (pin "C1") (pinfunction "C1_C1") (pintype "unspecified"))
      (node (ref "R28") (pin "2") (pinfunction "2_2") (pintype "input"))
      (node (ref "U2") (pin "12") (pinfunction "OUT0_12") (pintype "input"))
      (node (ref "U2") (pin "13") (pinfunction "OUT0_13") (pintype "input"))
      (node (ref "U2") (pin "14") (pinfunction "OUT0_14") (pintype "input"))
    )
    (net (code "11") (name "/OUT2") (class "Default")
      (node (ref "C10") (pin "2") (pinfunction "2_2") (pintype "unspecified"))
      (node (ref "CN3") (pin "A2") (pinfunction "A2_A2") (pintype "unspecified"))
      (node (ref "R29") (pin "2") (pinfunction "2_2") (pintype "input"))
      (node (ref "U2") (pin "10") (pinfunction "OUT1_10") (pintype "input"))
      (node (ref "U2") (pin "8") (pinfunction "OUT1_8") (pintype "input"))
      (node (ref "U2") (pin "9") (pinfunction "OUT1_9") (pintype "input"))
    )
    (net (code "12") (name "/OUT3") (class "Default")
      (node (ref "C9") (pin "2") (pinfunction "2_2") (pintype "unspecified"))
      (node (ref "CN3") (pin "A3") (pinfunction "A3_A3") (pintype "unspecified"))
      (node (ref "R30") (pin "2") (pinfunction "2_2") (pintype "input"))
      (node (ref "U3") (pin "12") (pinfunction "OUT0_12") (pintype "input"))
      (node (ref "U3") (pin "13") (pinfunction "OUT0_13") (pintype "input"))
      (node (ref "U3") (pin "14") (pinfunction "OUT0_14") (pintype "input"))
    )
    (net (code "13") (name "/OUT4") (class "Default")
      (node (ref "C11") (pin "2") (pinfunction "2_2") (pintype "unspecified"))
      (node (ref "CN3") (pin "A4") (pinfunction "A4_A4") (pintype "unspecified"))
      (node (ref "R31") (pin "2") (pinfunction "2_2") (pintype "input"))
      (node (ref "U3") (pin "10") (pinfunction "OUT1_10") (pintype "input"))
      (node (ref "U3") (pin "8") (pinfunction "OUT1_8") (pintype "input"))
      (node (ref "U3") (pin "9") (pinfunction "OUT1_9") (pintype "input"))
    )
    (net (code "14") (name "/OUT5") (class "Default")
      (node (ref "C14") (pin "2") (pinfunction "2_2") (pintype "unspecified"))
      (node (ref "CN3") (pin "A5") (pinfunction "A5_A5") (pintype "unspecified"))
      (node (ref "R32") (pin "2") (pinfunction "2_2") (pintype "input"))
      (node (ref "U4") (pin "12") (pinfunction "OUT0_12") (pintype "input"))
      (node (ref "U4") (pin "13") (pinfunction "OUT0_13") (pintype "input"))
      (node (ref "U4") (pin "14") (pinfunction "OUT0_14") (pintype "input"))
    )
    (net (code "15") (name "/OUT6") (class "Default")
      (node (ref "C16") (pin "2") (pinfunction "2_2") (pintype "unspecified"))
      (node (ref "CN3") (pin "A6") (pinfunction "A6_A6") (pintype "unspecified"))
      (node (ref "R33") (pin "2") (pinfunction "2_2") (pintype "input"))
      (node (ref "U4") (pin "10") (pinfunction "OUT1_10") (pintype "input"))
      (node (ref "U4") (pin "8") (pinfunction "OUT1_8") (pintype "input"))
      (node (ref "U4") (pin "9") (pinfunction "OUT1_9") (pintype "input"))
    )
    (net (code "16") (name "/OUT7") (class "Default")
      (node (ref "C15") (pin "2") (pinfunction "2_2") (pintype "unspecified"))
      (node (ref "CN3") (pin "A7") (pinfunction "A7_A7") (pintype "unspecified"))
      (node (ref "R34") (pin "2") (pinfunction "2_2") (pintype "input"))
      (node (ref "U5") (pin "12") (pinfunction "OUT0_12") (pintype "input"))
      (node (ref "U5") (pin "13") (pinfunction "OUT0_13") (pintype "input"))
      (node (ref "U5") (pin "14") (pinfunction "OUT0_14") (pintype "input"))
    )
    (net (code "17") (name "/OUT8") (class "Default")
      (node (ref "C17") (pin "2") (pinfunction "2_2") (pintype "unspecified"))
      (node (ref "CN3") (pin "C8") (pinfunction "C8_C8") (pintype "unspecified"))
      (node (ref "R35") (pin "2") (pinfunction "2_2") (pintype "input"))
      (node (ref "U5") (pin "10") (pinfunction "OUT1_10") (pintype "input"))
      (node (ref "U5") (pin "8") (pinfunction "OUT1_8") (pintype "input"))
      (node (ref "U5") (pin "9") (pinfunction "OUT1_9") (pintype "input"))
    )
    (net (code "18") (name "/OUT9") (class "Default")
      (node (ref "C20") (pin "2") (pinfunction "2_2") (pintype "unspecified"))
      (node (ref "CN3") (pin "B7") (pinfunction "B7_B7") (pintype "unspecified"))
      (node (ref "R36") (pin "2") (pinfunction "2_2") (pintype "input"))
      (node (ref "U6") (pin "12") (pinfunction "OUT0_12") (pintype "input"))
      (node (ref "U6") (pin "13") (pinfunction "OUT0_13") (pintype "input"))
      (node (ref "U6") (pin "14") (pinfunction "OUT0_14") (pintype "input"))
    )
    (net (code "19") (name "/OUT10") (class "Default")
      (node (ref "C22") (pin "2") (pinfunction "2_2") (pintype "unspecified"))
      (node (ref "CN3") (pin "B6") (pinfunction "B6_B6") (pintype "unspecified"))
      (node (ref "R37") (pin "2") (pinfunction "2_2") (pintype "input"))
      (node (ref "U6") (pin "10") (pinfunction "OUT1_10") (pintype "input"))
      (node (ref "U6") (pin "8") (pinfunction "OUT1_8") (pintype "input"))
      (node (ref "U6") (pin "9") (pinfunction "OUT1_9") (pintype "input"))
    )
    (net (code "20") (name "/OUT11") (class "Default")
      (node (ref "C21") (pin "2") (pinfunction "2_2") (pintype "unspecified"))
      (node (ref "CN3") (pin "C6") (pinfunction "C6_C6") (pintype "unspecified"))
      (node (ref "R38") (pin "2") (pinfunction "2_2") (pintype "input"))
      (node (ref "U7") (pin "12") (pinfunction "OUT0_12") (pintype "input"))
      (node (ref "U7") (pin "13") (pinfunction "OUT0_13") (pintype "input"))
      (node (ref "U7") (pin "14") (pinfunction "OUT0_14") (pintype "input"))
    )
    (net (code "21") (name "/OUT12") (class "Default")
      (node (ref "C23") (pin "2") (pinfunction "2_2") (pintype "unspecified"))
      (node (ref "CN3") (pin "C7") (pinfunction "C7_C7") (pintype "unspecified"))
      (node (ref "R39") (pin "2") (pinfunction "2_2") (pintype "input"))
      (node (ref "U7") (pin "10") (pinfunction "OUT1_10") (pintype "input"))
      (node (ref "U7") (pin "8") (pinfunction "OUT1_8") (pintype "input"))
      (node (ref "U7") (pin "9") (pinfunction "OUT1_9") (pintype "input"))
    )
    (net (code "22") (name "/PROFET_DEN1") (class "Default")
      (node (ref "R6") (pin "1") (pinfunction "1_1") (pintype "input"))
      (node (ref "U1") (pin "23") (pinfunction "IO21_23") (pintype "unspecified"))
    )
    (net (code "23") (name "/PROFET_DEN2") (class "Default")
      (node (ref "R7") (pin "1") (pinfunction "1_1") (pintype "input"))
      (node (ref "U1") (pin "20") (pinfunction "IO12_20") (pintype "unspecified"))
    )
    (net (code "24") (name "/PROFET_DEN3") (class "Default")
      (node (ref "R14") (pin "1") (pinfunction "1_1") (pintype "input"))
      (node (ref "U1") (pin "16") (pinfunction "IO46_16") (pintype "unspecified"))
    )
    (net (code "25") (name "/PROFET_DEN4") (class "Default")
      (node (ref "R15") (pin "1") (pinfunction "1_1") (pintype "input"))
      (node (ref "U1") (pin "11") (pinfunction "IO18_11") (pintype "unspecified"))
    )
    (net (code "26") (name "/PROFET_DEN5") (class "Default")
      (node (ref "R22") (pin "1") (pinfunction "1_1") (pintype "input"))
      (node (ref "U1") (pin "8") (pinfunction "IO15_8") (pintype "unspecified"))
    )
    (net (code "27") (name "/PROFET_DEN6") (class "Default")
      (node (ref "R23") (pin "1") (pinfunction "1_1") (pintype "input"))
      (node (ref "U1") (pin "5") (pinfunction "IO5_5") (pintype "unspecified"))
    )
    (net (code "28") (name "/PROFET_DSEL") (class "Default")
      (node (ref "R16") (pin "1") (pinfunction "1_1") (pintype "input"))
      (node (ref "R17") (pin "1") (pinfunction "1_1") (pintype "input"))
      (node (ref "R24") (pin "1") (pinfunction "1_1") (pintype "input"))
      (node (ref "R25") (pin "1") (pinfunction "1_1") (pintype "input"))
      (node (ref "R8") (pin "1") (pinfunction "1_1") (pintype "input"))
      (node (ref "R9") (pin "1") (pinfunction "1_1") (pintype "input"))
      (node (ref "U1") (pin "25") (pinfunction "IO48_25") (pintype "unspecified"))
    )
    (net (code "29") (name "/PROFET_IN1") (class "Default")
      (node (ref "R4") (pin "1") (pinfunction "1_1") (pintype "input"))
      (node (ref "U1") (pin "24") (pinfunction "IO47_24") (pintype "unspecified"))
    )
    (net (code "30") (name "/PROFET_IN2") (class "Default")
      (node (ref "R10") (pin "1") (pinfunction "1_1") (pintype "input"))
      (node (ref "U1") (pin "22") (pinfunction "IO14_22") (pintype "unspecified"))
    )
    (net (code "31") (name "/PROFET_IN3") (class "Default")
      (node (ref "R5") (pin "1") (pinfunction "1_1") (pintype "input"))
      (node (ref "U1") (pin "21") (pinfunction "IO13_21") (pintype "unspecified"))
    )
    (net (code "32") (name "/PROFET_IN4") (class "Default")
      (node (ref "R11") (pin "1") (pinfunction "1_1") (pintype "input"))
      (node (ref "U1") (pin "19") (pinfunction "IO11_19") (pintype "unspecified"))
    )
    (net (code "33") (name "/PROFET_IN5") (class "Default")
      (node (ref "R12") (pin "1") (pinfunction "1_1") (pintype "input"))
      (node (ref "U1") (pin "18") (pinfunction "IO10_18") (pintype "unspecified"))
    )
    (net (code "34") (name "/PROFET_IN6") (class "Default")
      (node (ref "R18") (pin "1") (pinfunction "1_1") (pintype "input"))
      (node (ref "U1") (pin "15") (pinfunction "IO3_15") (pintype "unspecified"))
    )
    (net (code "35") (name "/PROFET_IN7") (class "Default")
      (node (ref "R13") (pin "1") (pinfunction "1_1") (pintype "input"))
      (node (ref "U1") (pin "12") (pinfunction "IO8_12") (pintype "unspecified"))
    )
    (net (code "36") (name "/PROFET_IN8") (class "Default")
      (node (ref "R19") (pin "1") (pinfunction "1_1") (pintype "input"))
      (node (ref "U1") (pin "10") (pinfunction "IO17_10") (pintype "unspecified"))
    )
    (net (code "37") (name "/PROFET_IN9") (class "Default")
      (node (ref "R20") (pin "1") (pinfunction "1_1") (pintype "input"))
      (node (ref "U1") (pin "9") (pinfunction "IO16_9") (pintype "unspecified"))
    )
    (net (code "38") (name "/PROFET_IN10") (class "Default")
      (node (ref "R26") (pin "1") (pinfunction "1_1") (pintype "input"))
      (node (ref "U1") (pin "7") (pinfunction "IO7_7") (pintype "unspecified"))
    )
    (net (code "39") (name "/PROFET_IN11") (class "Default")
      (node (ref "R21") (pin "1") (pinfunction "1_1") (pintype "input"))
      (node (ref "U1") (pin "6") (pinfunction "IO6_6") (pintype "unspecified"))
    )
    (net (code "40") (name "/PROFET_IN12") (class "Default")
      (node (ref "R27") (pin "1") (pinfunction "1_1") (pintype "input"))
      (node (ref "U1") (pin "4") (pinfunction "IO4_4") (pintype "unspecified"))
    )
    (net (code "41") (name "/PROFET_IS") (class "Default")
      (node (ref "C4") (pin "2") (pinfunction "2_2") (pintype "input"))
      (node (ref "R2") (pin "2") (pinfunction "2_2") (pintype "input"))
      (node (ref "R3") (pin "2") (pinfunction "2_2") (pintype "input"))
      (node (ref "U2") (pin "4") (pinfunction "IS_4") (pintype "input"))
      (node (ref "U3") (pin "4") (pinfunction "IS_4") (pintype "input"))
      (node (ref "U4") (pin "4") (pinfunction "IS_4") (pintype "input"))
      (node (ref "U5") (pin "4") (pinfunction "IS_4") (pintype "input"))
      (node (ref "U6") (pin "4") (pinfunction "IS_4") (pintype "input"))
      (node (ref "U7") (pin "4") (pinfunction "IS_4") (pintype "input"))
    )
    (net (code "42") (name "/UART_RX") (class "Default")
      (node (ref "H1") (pin "2") (pinfunction "2_2") (pintype "unspecified"))
      (node (ref "U1") (pin "36") (pinfunction "RXD0_36") (pintype "unspecified"))
    )
    (net (code "43") (name "/UART_TX") (class "Default")
      (node (ref "H1") (pin "1") (pinfunction "1_1") (pintype "unspecified"))
      (node (ref "U1") (pin "37") (pinfunction "TXD0_37") (pintype "unspecified"))
    )
    (net (code "44") (name "/VBAT_PROT") (class "Default")
      (node (ref "C12") (pin "1") (pinfunction "1_1") (pintype "unspecified"))
      (node (ref "C13") (pin "1") (pinfunction "1_1") (pintype "unspecified"))
      (node (ref "C18") (pin "1") (pinfunction "1_1") (pintype "unspecified"))
      (node (ref "C19") (pin "1") (pinfunction "1_1") (pintype "unspecified"))
      (node (ref "C32") (pin "2") (pinfunction "2_2") (pintype "input"))
      (node (ref "C6") (pin "1") (pinfunction "1_1") (pintype "unspecified"))
      (node (ref "C7") (pin "1") (pinfunction "1_1") (pintype "unspecified"))
      (node (ref "CN3") (pin "A1") (pinfunction "A1_A1") (pintype "unspecified"))
      (node (ref "CN3") (pin "B1") (pinfunction "B1_B1") (pintype "unspecified"))
      (node (ref "D1") (pin "1") (pinfunction "K_1") (pintype "unspecified"))
      (node (ref "D2") (pin "2") (pinfunction "A_2") (pintype "unspecified"))
      (node (ref "R58") (pin "2") (pinfunction "2_2") (pintype "input"))
      (node (ref "U2") (pin "15") (pinfunction "VS_15") (pintype "input"))
      (node (ref "U3") (pin "15") (pinfunction "VS_15") (pintype "input"))
      (node (ref "U4") (pin "15") (pinfunction "VS_15") (pintype "input"))
      (node (ref "U5") (pin "15") (pinfunction "VS_15") (pintype "input"))
      (node (ref "U6") (pin "15") (pinfunction "VS_15") (pintype "input"))
      (node (ref "U7") (pin "15") (pinfunction "VS_15") (pintype "input"))
      (node (ref "U9") (pin "1") (pinfunction "1_1") (pintype "input"))
    )
    (net (code "45") (name "/VSENSE_BAT") (class "Default")
      (node (ref "C5") (pin "2") (pinfunction "2_2") (pintype "unspecified"))
      (node (ref "R57") (pin "2") (pinfunction "2_2") (pintype "input"))
      (node (ref "R58") (pin "1") (pinfunction "1_1") (pintype "input"))
      (node (ref "U1") (pin "39") (pinfunction "IO1_39") (pintype "unspecified"))
    )
    (net (code "46") (name "GND") (class "Default")
      (node (ref "C1") (pin "2") (pinfunction "2_2") (pintype "unspecified"))
      (node (ref "C10") (pin "1") (pinfunction "1_1") (pintype "unspecified"))
      (node (ref "C11") (pin "1") (pinfunction "1_1") (pintype "unspecified"))
      (node (ref "C12") (pin "2") (pinfunction "2_2") (pintype "unspecified"))
      (node (ref "C13") (pin "2") (pinfunction "2_2") (pintype "unspecified"))
      (node (ref "C14") (pin "1") (pinfunction "1_1") (pintype "unspecified"))
      (node (ref "C15") (pin "1") (pinfunction "1_1") (pintype "unspecified"))
      (node (ref "C16") (pin "1") (pinfunction "1_1") (pintype "unspecified"))
      (node (ref "C17") (pin "1") (pinfunction "1_1") (pintype "unspecified"))
      (node (ref "C18") (pin "2") (pinfunction "2_2") (pintype "unspecified"))
      (node (ref "C19") (pin "2") (pinfunction "2_2") (pintype "unspecified"))
      (node (ref "C2") (pin "2") (pinfunction "2_2") (pintype "unspecified"))
      (node (ref "C20") (pin "1") (pinfunction "1_1") (pintype "unspecified"))
      (node (ref "C21") (pin "1") (pinfunction "1_1") (pintype "unspecified"))
      (node (ref "C22") (pin "1") (pinfunction "1_1") (pintype "unspecified"))
      (node (ref "C23") (pin "1") (pinfunction "1_1") (pintype "unspecified"))
      (node (ref "C24") (pin "2") (pinfunction "2_2") (pintype "unspecified"))
      (node (ref "C25") (pin "2") (pinfunction "2_2") (pintype "unspecified"))
      (node (ref "C26") (pin "2") (pinfunction "2_2") (pintype "unspecified"))
      (node (ref "C27") (pin "2") (pinfunction "2_2") (pintype "unspecified"))
      (node (ref "C28") (pin "2") (pinfunction "2_2") (pintype "unspecified"))
      (node (ref "C29") (pin "2") (pinfunction "2_2") (pintype "unspecified"))
      (node (ref "C3") (pin "1") (pinfunction "1_1") (pintype "unspecified"))
      (node (ref "C30") (pin "2") (pinfunction "2_2") (pintype "unspecified"))
      (node (ref "C31") (pin "2") (pinfunction "2_2") (pintype "unspecified"))
      (node (ref "C32") (pin "1") (pinfunction "1_1") (pintype "input"))
      (node (ref "C33") (pin "1") (pinfunction "1_1") (pintype "unspecified"))
      (node (ref "C34") (pin "1") (pinfunction "1_1") (pintype "input"))
      (node (ref "C4") (pin "1") (pinfunction "1_1") (pintype "input"))
      (node (ref "C5") (pin "1") (pinfunction "1_1") (pintype "unspecified"))
      (node (ref "C6") (pin "2") (pinfunction "2_2") (pintype "unspecified"))
      (node (ref "C7") (pin "2") (pinfunction "2_2") (pintype "unspecified"))
      (node (ref "C8") (pin "1") (pinfunction "1_1") (pintype "unspecified"))
      (node (ref "C9") (pin "1") (pinfunction "1_1") (pintype "unspecified"))
      (node (ref "CN3") (pin "A8") (pinfunction "A8_A8") (pintype "unspecified"))
      (node (ref "CN3") (pin "B8") (pinfunction "B8_B8") (pintype "unspecified"))
      (node (ref "D1") (pin "2") (pinfunction "A_2") (pintype "unspecified"))
      (node (ref "H1") (pin "3") (pinfunction "3_3") (pintype "unspecified"))
      (node (ref "LED1") (pin "2") (pinfunction "K_2") (pintype "unspecified"))
      (node (ref "LED10") (pin "2") (pinfunction "K_2") (pintype "unspecified"))
      (node (ref "LED11") (pin "2") (pinfunction "K_2") (pintype "unspecified"))
      (node (ref "LED12") (pin "2") (pinfunction "K_2") (pintype "unspecified"))
      (node (ref "LED13") (pin "2") (pinfunction "K_2") (pintype "unspecified"))
      (node (ref "LED2") (pin "2") (pinfunction "K_2") (pintype "unspecified"))
      (node (ref "LED3") (pin "2") (pinfunction "K_2") (pintype "unspecified"))
      (node (ref "LED4") (pin "2") (pinfunction "K_2") (pintype "unspecified"))
      (node (ref "LED5") (pin "2") (pinfunction "K_2") (pintype "unspecified"))
      (node (ref "LED6") (pin "2") (pinfunction "K_2") (pintype "unspecified"))
      (node (ref "LED7") (pin "2") (pinfunction "K_2") (pintype "unspecified"))
      (node (ref "LED8") (pin "2") (pinfunction "K_2") (pintype "unspecified"))
      (node (ref "LED9") (pin "2") (pinfunction "K_2") (pintype "unspecified"))
      (node (ref "R3") (pin "1") (pinfunction "1_1") (pintype "input"))
      (node (ref "R57") (pin "1") (pinfunction "1_1") (pintype "input"))
      (node (ref "SW1") (pin "3") (pinfunction "C_3") (pintype "unspecified"))
      (node (ref "SW2") (pin "3") (pinfunction "C_3") (pintype "unspecified"))
      (node (ref "U1") (pin "1") (pinfunction "GND_1") (pintype "unspecified"))
      (node (ref "U1") (pin "40") (pinfunction "GND_40") (pintype "unspecified"))
      (node (ref "U1") (pin "41") (pinfunction "GND_41") (pintype "unspecified"))
      (node (ref "U10") (pin "2") (pinfunction "GND_2") (pintype "unspecified"))
      (node (ref "U2") (pin "1") (pinfunction "GND_1") (pintype "input"))
      (node (ref "U3") (pin "1") (pinfunction "GND_1") (pintype "input"))
      (node (ref "U4") (pin "1") (pinfunction "GND_1") (pintype "input"))
      (node (ref "U5") (pin "1") (pinfunction "GND_1") (pintype "input"))
      (node (ref "U6") (pin "1") (pinfunction "GND_1") (pintype "input"))
      (node (ref "U7") (pin "1") (pinfunction "GND_1") (pintype "input"))
      (node (ref "U9") (pin "2") (pinfunction "2_2") (pintype "input"))
    )
    (net (code "47") (name "Net-(C24-Pad1)") (class "Default")
      (node (ref "C24") (pin "1") (pinfunction "1_1") (pintype "unspecified"))
      (node (ref "CN3") (pin "B3") (pinfunction "B3_B3") (pintype "unspecified"))
      (node (ref "R43") (pin "1") (pinfunction "1_1") (pintype "input"))
      (node (ref "R54") (pin "1") (pinfunction "1_1") (pintype "input"))
    )
    (net (code "48") (name "Net-(C25-Pad1)") (class "Default")
      (node (ref "C25") (pin "1") (pinfunction "1_1") (pintype "unspecified"))
      (node (ref "CN3") (pin "B2") (pinfunction "B2_B2") (pintype "unspecified"))
      (node (ref "R45") (pin "1") (pinfunction "1_1") (pintype "input"))
      (node (ref "R52") (pin "1") (pinfunction "1_1") (pintype "input"))
    )
    (net (code "49") (name "Net-(C26-Pad1)") (class "Default")
      (node (ref "C26") (pin "1") (pinfunction "1_1") (pintype "unspecified"))
      (node (ref "CN3") (pin "C2") (pinfunction "C2_C2") (pintype "unspecified"))
      (node (ref "R42") (pin "1") (pinfunction "1_1") (pintype "input"))
      (node (ref "R56") (pin "1") (pinfunction "1_1") (pintype "input"))
    )
    (net (code "50") (name "Net-(C27-Pad1)") (class "Default")
      (node (ref "C27") (pin "1") (pinfunction "1_1") (pintype "unspecified"))
      (node (ref "CN3") (pin "B5") (pinfunction "B5_B5") (pintype "unspecified"))
      (node (ref "R46") (pin "1") (pinfunction "1_1") (pintype "input"))
      (node (ref "R49") (pin "1") (pinfunction "1_1") (pintype "input"))
    )
    (net (code "51") (name "Net-(C28-Pad1)") (class "Default")
      (node (ref "C28") (pin "1") (pinfunction "1_1") (pintype "unspecified"))
      (node (ref "CN3") (pin "C5") (pinfunction "C5_C5") (pintype "unspecified"))
      (node (ref "R44") (pin "1") (pinfunction "1_1") (pintype "input"))
      (node (ref "R50") (pin "1") (pinfunction "1_1") (pintype "input"))
    )
    (net (code "52") (name "Net-(C29-Pad1)") (class "Default")
      (node (ref "C29") (pin "1") (pinfunction "1_1") (pintype "unspecified"))
      (node (ref "CN3") (pin "B4") (pinfunction "B4_B4") (pintype "unspecified"))
      (node (ref "R41") (pin "1") (pinfunction "1_1") (pintype "input"))
      (node (ref "R55") (pin "1") (pinfunction "1_1") (pintype "input"))
    )
    (net (code "53") (name "Net-(C30-Pad1)") (class "Default")
      (node (ref "C30") (pin "1") (pinfunction "1_1") (pintype "unspecified"))
      (node (ref "CN3") (pin "C3") (pinfunction "C3_C3") (pintype "unspecified"))
      (node (ref "R48") (pin "1") (pinfunction "1_1") (pintype "input"))
      (node (ref "R53") (pin "1") (pinfunction "1_1") (pintype "input"))
    )
    (net (code "54") (name "Net-(C31-Pad1)") (class "Default")
      (node (ref "C31") (pin "1") (pinfunction "1_1") (pintype "unspecified"))
      (node (ref "CN3") (pin "C4") (pinfunction "C4_C4") (pintype "unspecified"))
      (node (ref "R47") (pin "1") (pinfunction "1_1") (pintype "input"))
      (node (ref "R51") (pin "1") (pinfunction "1_1") (pintype "input"))
    )
    (net (code "55") (name "Net-(D2-K)") (class "Default")
      (node (ref "C34") (pin "2") (pinfunction "2_2") (pintype "input"))
      (node (ref "D2") (pin "1") (pinfunction "K_1") (pintype "unspecified"))
      (node (ref "U10") (pin "1") (pinfunction "VIN_1") (pintype "unspecified"))
    )
    (net (code "56") (name "Net-(LED1-A)") (class "Default")
      (node (ref "LED1") (pin "1") (pinfunction "A_1") (pintype "unspecified"))
      (node (ref "R28") (pin "1") (pinfunction "1_1") (pintype "input"))
    )
    (net (code "57") (name "Net-(LED2-A)") (class "Default")
      (node (ref "LED2") (pin "1") (pinfunction "A_1") (pintype "unspecified"))
      (node (ref "R29") (pin "1") (pinfunction "1_1") (pintype "input"))
    )
    (net (code "58") (name "Net-(LED3-A)") (class "Default")
      (node (ref "LED3") (pin "1") (pinfunction "A_1") (pintype "unspecified"))
      (node (ref "R30") (pin "1") (pinfunction "1_1") (pintype "input"))
    )
    (net (code "59") (name "Net-(LED4-A)") (class "Default")
      (node (ref "LED4") (pin "1") (pinfunction "A_1") (pintype "unspecified"))
      (node (ref "R31") (pin "1") (pinfunction "1_1") (pintype "input"))
    )
    (net (code "60") (name "Net-(LED5-A)") (class "Default")
      (node (ref "LED5") (pin "1") (pinfunction "A_1") (pintype "unspecified"))
      (node (ref "R32") (pin "1") (pinfunction "1_1") (pintype "input"))
    )
    (net (code "61") (name "Net-(LED6-A)") (class "Default")
      (node (ref "LED6") (pin "1") (pinfunction "A_1") (pintype "unspecified"))
      (node (ref "R33") (pin "1") (pinfunction "1_1") (pintype "input"))
    )
    (net (code "62") (name "Net-(LED7-A)") (class "Default")
      (node (ref "LED7") (pin "1") (pinfunction "A_1") (pintype "unspecified"))
      (node (ref "R34") (pin "1") (pinfunction "1_1") (pintype "input"))
    )
    (net (code "63") (name "Net-(LED8-A)") (class "Default")
      (node (ref "LED8") (pin "1") (pinfunction "A_1") (pintype "unspecified"))
      (node (ref "R35") (pin "1") (pinfunction "1_1") (pintype "input"))
    )
    (net (code "64") (name "Net-(LED9-A)") (class "Default")
      (node (ref "LED9") (pin "1") (pinfunction "A_1") (pintype "unspecified"))
      (node (ref "R36") (pin "1") (pinfunction "1_1") (pintype "input"))
    )
    (net (code "65") (name "Net-(LED10-A)") (class "Default")
      (node (ref "LED10") (pin "1") (pinfunction "A_1") (pintype "unspecified"))
      (node (ref "R37") (pin "1") (pinfunction "1_1") (pintype "input"))
    )
    (net (code "66") (name "Net-(LED11-A)") (class "Default")
      (node (ref "LED11") (pin "1") (pinfunction "A_1") (pintype "unspecified"))
      (node (ref "R38") (pin "1") (pinfunction "1_1") (pintype "input"))
    )
    (net (code "67") (name "Net-(LED12-A)") (class "Default")
      (node (ref "LED12") (pin "1") (pinfunction "A_1") (pintype "unspecified"))
      (node (ref "R39") (pin "1") (pinfunction "1_1") (pintype "input"))
    )
    (net (code "68") (name "Net-(LED13-A)") (class "Default")
      (node (ref "LED13") (pin "1") (pinfunction "A_1") (pintype "unspecified"))
      (node (ref "R40") (pin "1") (pinfunction "1_1") (pintype "input"))
    )
    (net (code "69") (name "Net-(SW1-B)") (class "Default")
      (node (ref "C3") (pin "2") (pinfunction "2_2") (pintype "unspecified"))
      (node (ref "R1") (pin "2") (pinfunction "2_2") (pintype "input"))
      (node (ref "SW1") (pin "2") (pinfunction "B_2") (pintype "unspecified"))
      (node (ref "U1") (pin "3") (pinfunction "EN_3") (pintype "unspecified"))
    )
    (net (code "70") (name "Net-(SW2-A)") (class "Default")
      (node (ref "SW2") (pin "1") (pinfunction "A_1") (pintype "unspecified"))
      (node (ref "U1") (pin "27") (pinfunction "IO0_27") (pintype "unspecified"))
    )
    (net (code "71") (name "Net-(U1-IO9)") (class "Default")
      (node (ref "R2") (pin "1") (pinfunction "1_1") (pintype "input"))
      (node (ref "U1") (pin "17") (pinfunction "IO9_17") (pintype "unspecified"))
    )
    (net (code "72") (name "Net-(U2-DEN)") (class "Default")
      (node (ref "R6") (pin "2") (pinfunction "2_2") (pintype "input"))
      (node (ref "U2") (pin "3") (pinfunction "DEN_3") (pintype "input"))
    )
    (net (code "73") (name "Net-(U2-DSEL)") (class "Default")
      (node (ref "R8") (pin "2") (pinfunction "2_2") (pintype "input"))
      (node (ref "U2") (pin "5") (pinfunction "DSEL_5") (pintype "input"))
    )
    (net (code "74") (name "Net-(U2-IN0)") (class "Default")
      (node (ref "R4") (pin "2") (pinfunction "2_2") (pintype "input"))
      (node (ref "U2") (pin "2") (pinfunction "IN0_2") (pintype "input"))
    )
    (net (code "75") (name "Net-(U2-IN1)") (class "Default")
      (node (ref "R10") (pin "2") (pinfunction "2_2") (pintype "input"))
      (node (ref "U2") (pin "6") (pinfunction "IN1_6") (pintype "input"))
    )
    (net (code "76") (name "Net-(U3-DEN)") (class "Default")
      (node (ref "R7") (pin "2") (pinfunction "2_2") (pintype "input"))
      (node (ref "U3") (pin "3") (pinfunction "DEN_3") (pintype "input"))
    )
    (net (code "77") (name "Net-(U3-DSEL)") (class "Default")
      (node (ref "R9") (pin "2") (pinfunction "2_2") (pintype "input"))
      (node (ref "U3") (pin "5") (pinfunction "DSEL_5") (pintype "input"))
    )
    (net (code "78") (name "Net-(U3-IN0)") (class "Default")
      (node (ref "R5") (pin "2") (pinfunction "2_2") (pintype "input"))
      (node (ref "U3") (pin "2") (pinfunction "IN0_2") (pintype "input"))
    )
    (net (code "79") (name "Net-(U3-IN1)") (class "Default")
      (node (ref "R11") (pin "2") (pinfunction "2_2") (pintype "input"))
      (node (ref "U3") (pin "6") (pinfunction "IN1_6") (pintype "input"))
    )
    (net (code "80") (name "Net-(U4-DEN)") (class "Default")
      (node (ref "R14") (pin "2") (pinfunction "2_2") (pintype "input"))
      (node (ref "U4") (pin "3") (pinfunction "DEN_3") (pintype "input"))
    )
    (net (code "81") (name "Net-(U4-DSEL)") (class "Default")
      (node (ref "R16") (pin "2") (pinfunction "2_2") (pintype "input"))
      (node (ref "U4") (pin "5") (pinfunction "DSEL_5") (pintype "input"))
    )
    (net (code "82") (name "Net-(U4-IN0)") (class "Default")
      (node (ref "R12") (pin "2") (pinfunction "2_2") (pintype "input"))
      (node (ref "U4") (pin "2") (pinfunction "IN0_2") (pintype "input"))
    )
    (net (code "83") (name "Net-(U4-IN1)") (class "Default")
      (node (ref "R18") (pin "2") (pinfunction "2_2") (pintype "input"))
      (node (ref "U4") (pin "6") (pinfunction "IN1_6") (pintype "input"))
    )
    (net (code "84") (name "Net-(U5-DEN)") (class "Default")
      (node (ref "R15") (pin "2") (pinfunction "2_2") (pintype "input"))
      (node (ref "U5") (pin "3") (pinfunction "DEN_3") (pintype "input"))
    )
    (net (code "85") (name "Net-(U5-DSEL)") (class "Default")
      (node (ref "R17") (pin "2") (pinfunction "2_2") (pintype "input"))
      (node (ref "U5") (pin "5") (pinfunction "DSEL_5") (pintype "input"))
    )
    (net (code "86") (name "Net-(U5-IN0)") (class "Default")
      (node (ref "R13") (pin "2") (pinfunction "2_2") (pintype "input"))
      (node (ref "U5") (pin "2") (pinfunction "IN0_2") (pintype "input"))
    )
    (net (code "87") (name "Net-(U5-IN1)") (class "Default")
      (node (ref "R19") (pin "2") (pinfunction "2_2") (pintype "input"))
      (node (ref "U5") (pin "6") (pinfunction "IN1_6") (pintype "input"))
    )
    (net (code "88") (name "Net-(U6-DEN)") (class "Default")
      (node (ref "R22") (pin "2") (pinfunction "2_2") (pintype "input"))
      (node (ref "U6") (pin "3") (pinfunction "DEN_3") (pintype "input"))
    )
    (net (code "89") (name "Net-(U6-DSEL)") (class "Default")
      (node (ref "R24") (pin "2") (pinfunction "2_2") (pintype "input"))
      (node (ref "U6") (pin "5") (pinfunction "DSEL_5") (pintype "input"))
    )
    (net (code "90") (name "Net-(U6-IN0)") (class "Default")
      (node (ref "R20") (pin "2") (pinfunction "2_2") (pintype "input"))
      (node (ref "U6") (pin "2") (pinfunction "IN0_2") (pintype "input"))
    )
    (net (code "91") (name "Net-(U6-IN1)") (class "Default")
      (node (ref "R26") (pin "2") (pinfunction "2_2") (pintype "input"))
      (node (ref "U6") (pin "6") (pinfunction "IN1_6") (pintype "input"))
    )
    (net (code "92") (name "Net-(U7-DEN)") (class "Default")
      (node (ref "R23") (pin "2") (pinfunction "2_2") (pintype "input"))
      (node (ref "U7") (pin "3") (pinfunction "DEN_3") (pintype "input"))
    )
    (net (code "93") (name "Net-(U7-DSEL)") (class "Default")
      (node (ref "R25") (pin "2") (pinfunction "2_2") (pintype "input"))
      (node (ref "U7") (pin "5") (pinfunction "DSEL_5") (pintype "input"))
    )
    (net (code "94") (name "Net-(U7-IN0)") (class "Default")
      (node (ref "R21") (pin "2") (pinfunction "2_2") (pintype "input"))
      (node (ref "U7") (pin "2") (pinfunction "IN0_2") (pintype "input"))
    )
    (net (code "95") (name "Net-(U7-IN1)") (class "Default")
      (node (ref "R27") (pin "2") (pinfunction "2_2") (pintype "input"))
      (node (ref "U7") (pin "6") (pinfunction "IN1_6") (pintype "input"))
    )
    (net (code "96") (name "unconnected-(SCREW1-Pad1)") (class "Default")
      (node (ref "SCREW1") (pin "1") (pinfunction "1_1") (pintype "input"))
    )
    (net (code "97") (name "unconnected-(SCREW2-Pad1)") (class "Default")
      (node (ref "SCREW2") (pin "1") (pinfunction "1_1") (pintype "input"))
    )
    (net (code "98") (name "unconnected-(SCREW3-Pad1)") (class "Default")
      (node (ref "SCREW3") (pin "1") (pinfunction "1_1") (pintype "input"))
    )
    (net (code "99") (name "unconnected-(SCREW4-Pad1)") (class "Default")
      (node (ref "SCREW4") (pin "1") (pinfunction "1_1") (pintype "input"))
    )
    (net (code "100") (name "unconnected-(SW1-A-Pad1)") (class "Default")
      (node (ref "SW1") (pin "1") (pinfunction "A_1") (pintype "unspecified+no_connect"))
    )
    (net (code "101") (name "unconnected-(SW1-D-Pad4)") (class "Default")
      (node (ref "SW1") (pin "4") (pinfunction "D_4") (pintype "unspecified+no_connect"))
    )
    (net (code "102") (name "unconnected-(SW2-B-Pad2)") (class "Default")
      (node (ref "SW2") (pin "2") (pinfunction "B_2") (pintype "unspecified+no_connect"))
    )
    (net (code "103") (name "unconnected-(SW2-D-Pad4)") (class "Default")
      (node (ref "SW2") (pin "4") (pinfunction "D_4") (pintype "unspecified+no_connect"))
    )
    (net (code "104") (name "unconnected-(U1-IO2-Pad38)") (class "Default")
      (node (ref "U1") (pin "38") (pinfunction "IO2_38") (pintype "unspecified+no_connect"))
    )
    (net (code "105") (name "unconnected-(U1-IO19-Pad13)") (class "Default")
      (node (ref "U1") (pin "13") (pinfunction "IO19_13") (pintype "unspecified+no_connect"))
    )
    (net (code "106") (name "unconnected-(U1-IO20-Pad14)") (class "Default")
      (node (ref "U1") (pin "14") (pinfunction "IO20_14") (pintype "unspecified+no_connect"))
    )
    (net (code "107") (name "unconnected-(U1-IO45-Pad26)") (class "Default")
      (node (ref "U1") (pin "26") (pinfunction "IO45_26") (pintype "unspecified+no_connect"))
    )
    (net (code "108") (name "unconnected-(U2-n.c.-Pad7)") (class "Default")
      (node (ref "U2") (pin "7") (pinfunction "n.c._7") (pintype "input+no_connect"))
    )
    (net (code "109") (name "unconnected-(U2-n.c.-Pad11)") (class "Default")
      (node (ref "U2") (pin "11") (pinfunction "n.c._11") (pintype "input+no_connect"))
    )
    (net (code "110") (name "unconnected-(U3-n.c.-Pad7)") (class "Default")
      (node (ref "U3") (pin "7") (pinfunction "n.c._7") (pintype "input+no_connect"))
    )
    (net (code "111") (name "unconnected-(U3-n.c.-Pad11)") (class "Default")
      (node (ref "U3") (pin "11") (pinfunction "n.c._11") (pintype "input+no_connect"))
    )
    (net (code "112") (name "unconnected-(U4-n.c.-Pad7)") (class "Default")
      (node (ref "U4") (pin "7") (pinfunction "n.c._7") (pintype "input+no_connect"))
    )
    (net (code "113") (name "unconnected-(U4-n.c.-Pad11)") (class "Default")
      (node (ref "U4") (pin "11") (pinfunction "n.c._11") (pintype "input+no_connect"))
    )
    (net (code "114") (name "unconnected-(U5-n.c.-Pad7)") (class "Default")
      (node (ref "U5") (pin "7") (pinfunction "n.c._7") (pintype "input+no_connect"))
    )
    (net (code "115") (name "unconnected-(U5-n.c.-Pad11)") (class "Default")
      (node (ref "U5") (pin "11") (pinfunction "n.c._11") (pintype "input+no_connect"))
    )
    (net (code "116") (name "unconnected-(U6-n.c.-Pad7)") (class "Default")
      (node (ref "U6") (pin "7") (pinfunction "n.c._7") (pintype "input+no_connect"))
    )
    (net (code "117") (name "unconnected-(U6-n.c.-Pad11)") (class "Default")
      (node (ref "U6") (pin "11") (pinfunction "n.c._11") (pintype "input+no_connect"))
    )
    (net (code "118") (name "unconnected-(U7-n.c.-Pad7)") (class "Default")
      (node (ref "U7") (pin "7") (pinfunction "n.c._7") (pintype "input+no_connect"))
    )
    (net (code "119") (name "unconnected-(U7-n.c.-Pad11)") (class "Default")
      (node (ref "U7") (pin "11") (pinfunction "n.c._11") (pintype "input+no_connect"))
    )
  )
)
